# STM32F4_TFT-Proto_Adapter_FSMC.net
KiCad netlist of a schematic drawn in EAGLE
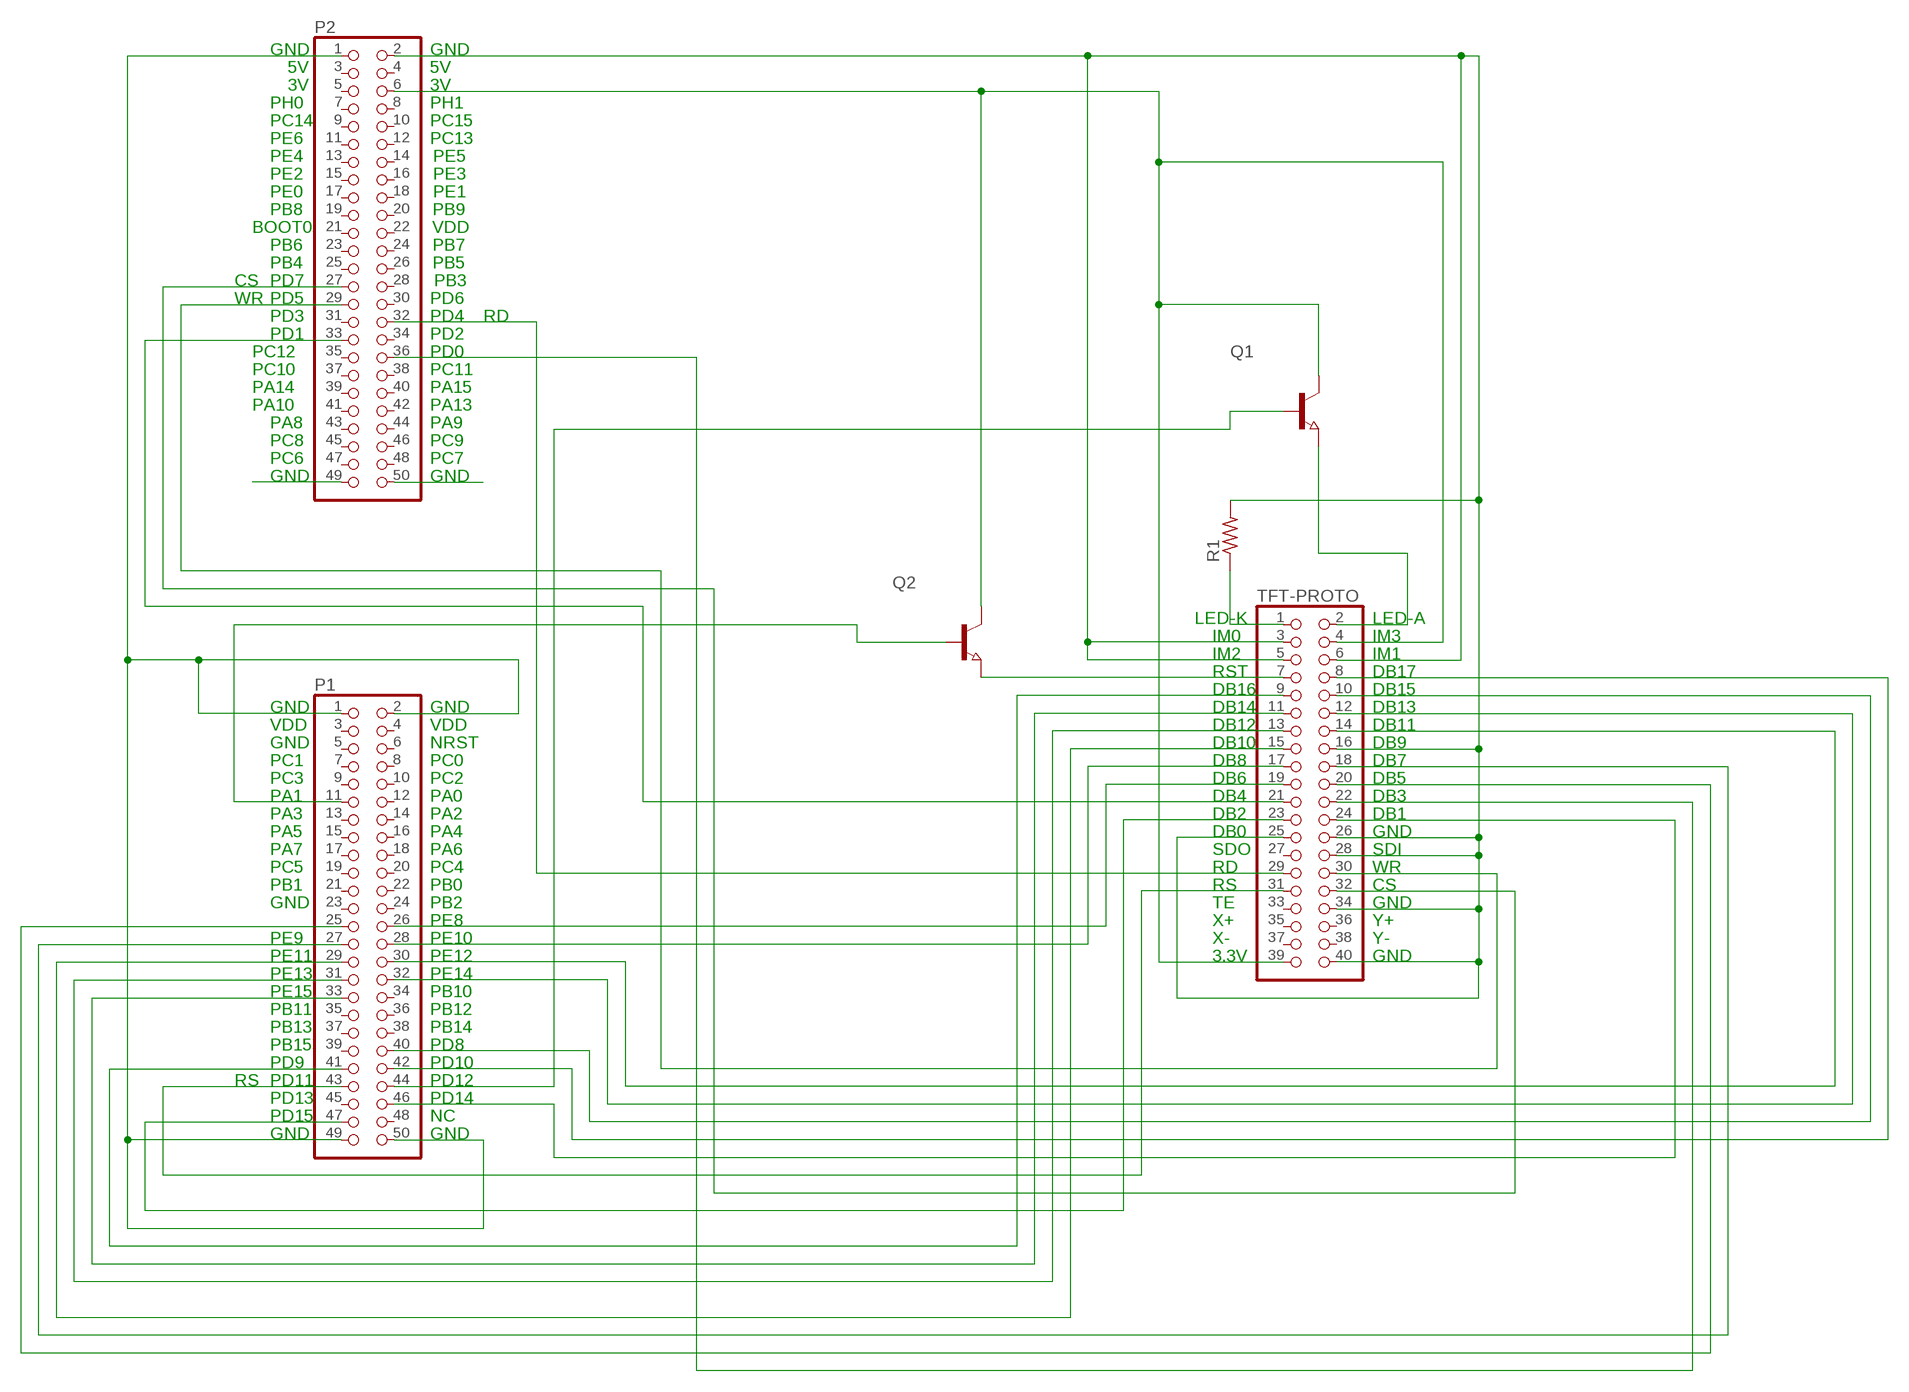
[diagram p0: schematic, sheet 1]

(export (version "E")
  (design (tool "Eeschema 10.0.6"))
  (components
    (comp (ref "P1")
      (value "PINHD-2X25")
      (footprint "eagle-import:2X25")
      (libsource (lib "eagle-import") (part "PINHD-2X25"))
    )
    (comp (ref "P2")
      (value "PINHD-2X25")
      (footprint "eagle-import:2X25")
      (libsource (lib "eagle-import") (part "PINHD-2X25"))
    )
    (comp (ref "Q1")
      (value "NPN-TRANSISTOR_SOT23")
      (footprint "eagle-import:SOT23")
      (libsource (lib "eagle-import") (part "NPN-TRANSISTOR_SOT23"))
    )
    (comp (ref "Q2")
      (value "NPN-TRANSISTOR_SOT23")
      (footprint "eagle-import:SOT23")
      (libsource (lib "eagle-import") (part "NPN-TRANSISTOR_SOT23"))
    )
    (comp (ref "R1")
      (value "R-US_R0805")
      (footprint "eagle-import:R0805")
      (libsource (lib "eagle-import") (part "R-US_R0805"))
    )
    (comp (ref "TFT-PROTO")
      (value "PINHD-2X20")
      (footprint "eagle-import:2X20")
      (libsource (lib "eagle-import") (part "PINHD-2X20"))
    )
  )
  (nets
    (net (code "1") (name "/GND") (class "Default")
      (node (ref "P1") (pin "1") (pinfunction "1_1") (pintype "passive"))
      (node (ref "P1") (pin "2") (pinfunction "2_2") (pintype "passive"))
      (node (ref "P1") (pin "49") (pinfunction "49_49") (pintype "passive"))
      (node (ref "P1") (pin "50") (pinfunction "50_50") (pintype "passive"))
      (node (ref "P2") (pin "1") (pinfunction "1_1") (pintype "passive"))
      (node (ref "P2") (pin "2") (pinfunction "2_2") (pintype "passive"))
      (node (ref "P2") (pin "49") (pinfunction "49_49") (pintype "passive"))
      (node (ref "P2") (pin "50") (pinfunction "50_50") (pintype "passive"))
      (node (ref "R1") (pin "2") (pinfunction "2_2") (pintype "passive"))
      (node (ref "TFT-PROTO") (pin "16") (pinfunction "16_16") (pintype "passive"))
      (node (ref "TFT-PROTO") (pin "25") (pinfunction "25_25") (pintype "passive"))
      (node (ref "TFT-PROTO") (pin "26") (pinfunction "26_26") (pintype "passive"))
      (node (ref "TFT-PROTO") (pin "28") (pinfunction "28_28") (pintype "passive"))
      (node (ref "TFT-PROTO") (pin "3") (pinfunction "3_3") (pintype "passive"))
      (node (ref "TFT-PROTO") (pin "34") (pinfunction "34_34") (pintype "passive"))
      (node (ref "TFT-PROTO") (pin "40") (pinfunction "40_40") (pintype "passive"))
      (node (ref "TFT-PROTO") (pin "5") (pinfunction "5_5") (pintype "passive"))
      (node (ref "TFT-PROTO") (pin "6") (pinfunction "6_6") (pintype "passive"))
    )
    (net (code "2") (name "Net-(P1-Pad25)") (class "Default")
      (node (ref "P1") (pin "25") (pinfunction "25_25") (pintype "passive"))
      (node (ref "TFT-PROTO") (pin "20") (pinfunction "20_20") (pintype "passive"))
    )
    (net (code "3") (name "Net-(P1-Pad26)") (class "Default")
      (node (ref "P1") (pin "26") (pinfunction "26_26") (pintype "passive"))
      (node (ref "TFT-PROTO") (pin "19") (pinfunction "19_19") (pintype "passive"))
    )
    (net (code "4") (name "Net-(P1-Pad27)") (class "Default")
      (node (ref "P1") (pin "27") (pinfunction "27_27") (pintype "passive"))
      (node (ref "TFT-PROTO") (pin "18") (pinfunction "18_18") (pintype "passive"))
    )
    (net (code "5") (name "Net-(P1-Pad28)") (class "Default")
      (node (ref "P1") (pin "28") (pinfunction "28_28") (pintype "passive"))
      (node (ref "TFT-PROTO") (pin "17") (pinfunction "17_17") (pintype "passive"))
    )
    (net (code "6") (name "Net-(P1-Pad29)") (class "Default")
      (node (ref "P1") (pin "29") (pinfunction "29_29") (pintype "passive"))
      (node (ref "TFT-PROTO") (pin "15") (pinfunction "15_15") (pintype "passive"))
    )
    (net (code "7") (name "Net-(P1-Pad30)") (class "Default")
      (node (ref "P1") (pin "30") (pinfunction "30_30") (pintype "passive"))
      (node (ref "TFT-PROTO") (pin "14") (pinfunction "14_14") (pintype "passive"))
    )
    (net (code "8") (name "Net-(P1-Pad31)") (class "Default")
      (node (ref "P1") (pin "31") (pinfunction "31_31") (pintype "passive"))
      (node (ref "TFT-PROTO") (pin "13") (pinfunction "13_13") (pintype "passive"))
    )
    (net (code "9") (name "Net-(P1-Pad32)") (class "Default")
      (node (ref "P1") (pin "32") (pinfunction "32_32") (pintype "passive"))
      (node (ref "TFT-PROTO") (pin "12") (pinfunction "12_12") (pintype "passive"))
    )
    (net (code "10") (name "Net-(P1-Pad33)") (class "Default")
      (node (ref "P1") (pin "33") (pinfunction "33_33") (pintype "passive"))
      (node (ref "TFT-PROTO") (pin "11") (pinfunction "11_11") (pintype "passive"))
    )
    (net (code "11") (name "Net-(P1-Pad40)") (class "Default")
      (node (ref "P1") (pin "40") (pinfunction "40_40") (pintype "passive"))
      (node (ref "TFT-PROTO") (pin "10") (pinfunction "10_10") (pintype "passive"))
    )
    (net (code "12") (name "Net-(P1-Pad41)") (class "Default")
      (node (ref "P1") (pin "41") (pinfunction "41_41") (pintype "passive"))
      (node (ref "TFT-PROTO") (pin "9") (pinfunction "9_9") (pintype "passive"))
    )
    (net (code "13") (name "Net-(P1-Pad42)") (class "Default")
      (node (ref "P1") (pin "42") (pinfunction "42_42") (pintype "passive"))
      (node (ref "TFT-PROTO") (pin "8") (pinfunction "8_8") (pintype "passive"))
    )
    (net (code "14") (name "Net-(P1-Pad43)") (class "Default")
      (node (ref "P1") (pin "43") (pinfunction "43_43") (pintype "passive"))
      (node (ref "TFT-PROTO") (pin "31") (pinfunction "31_31") (pintype "passive"))
    )
    (net (code "15") (name "Net-(P1-Pad46)") (class "Default")
      (node (ref "P1") (pin "46") (pinfunction "46_46") (pintype "passive"))
      (node (ref "TFT-PROTO") (pin "24") (pinfunction "24_24") (pintype "passive"))
    )
    (net (code "16") (name "Net-(P1-Pad47)") (class "Default")
      (node (ref "P1") (pin "47") (pinfunction "47_47") (pintype "passive"))
      (node (ref "TFT-PROTO") (pin "23") (pinfunction "23_23") (pintype "passive"))
    )
    (net (code "17") (name "Net-(P2-Pad27)") (class "Default")
      (node (ref "P2") (pin "27") (pinfunction "27_27") (pintype "passive"))
      (node (ref "TFT-PROTO") (pin "32") (pinfunction "32_32") (pintype "passive"))
    )
    (net (code "18") (name "Net-(P2-Pad29)") (class "Default")
      (node (ref "P2") (pin "29") (pinfunction "29_29") (pintype "passive"))
      (node (ref "TFT-PROTO") (pin "30") (pinfunction "30_30") (pintype "passive"))
    )
    (net (code "19") (name "Net-(P2-Pad32)") (class "Default")
      (node (ref "P2") (pin "32") (pinfunction "32_32") (pintype "passive"))
      (node (ref "TFT-PROTO") (pin "29") (pinfunction "29_29") (pintype "passive"))
    )
    (net (code "20") (name "Net-(P2-Pad33)") (class "Default")
      (node (ref "P2") (pin "33") (pinfunction "33_33") (pintype "passive"))
      (node (ref "TFT-PROTO") (pin "21") (pinfunction "21_21") (pintype "passive"))
    )
    (net (code "21") (name "Net-(P2-Pad36)") (class "Default")
      (node (ref "P2") (pin "36") (pinfunction "36_36") (pintype "passive"))
      (node (ref "TFT-PROTO") (pin "22") (pinfunction "22_22") (pintype "passive"))
    )
    (net (code "22") (name "Net-(Q1-B)") (class "Default")
      (node (ref "P1") (pin "44") (pinfunction "44_44") (pintype "passive"))
      (node (ref "Q1") (pin "1") (pinfunction "B_1") (pintype "passive"))
    )
    (net (code "23") (name "Net-(Q1-C)") (class "Default")
      (node (ref "P2") (pin "6") (pinfunction "6_6") (pintype "passive"))
      (node (ref "Q1") (pin "3") (pinfunction "C_3") (pintype "passive"))
      (node (ref "Q2") (pin "3") (pinfunction "C_3") (pintype "passive"))
      (node (ref "TFT-PROTO") (pin "39") (pinfunction "39_39") (pintype "passive"))
      (node (ref "TFT-PROTO") (pin "4") (pinfunction "4_4") (pintype "passive"))
    )
    (net (code "24") (name "Net-(Q1-E)") (class "Default")
      (node (ref "Q1") (pin "2") (pinfunction "E_2") (pintype "passive"))
      (node (ref "TFT-PROTO") (pin "2") (pinfunction "2_2") (pintype "passive"))
    )
    (net (code "25") (name "Net-(Q2-B)") (class "Default")
      (node (ref "P1") (pin "11") (pinfunction "11_11") (pintype "passive"))
      (node (ref "Q2") (pin "1") (pinfunction "B_1") (pintype "passive"))
    )
    (net (code "26") (name "Net-(Q2-E)") (class "Default")
      (node (ref "Q2") (pin "2") (pinfunction "E_2") (pintype "passive"))
      (node (ref "TFT-PROTO") (pin "7") (pinfunction "7_7") (pintype "passive"))
    )
    (net (code "27") (name "Net-(R1-Pad1)") (class "Default")
      (node (ref "R1") (pin "1") (pinfunction "1_1") (pintype "passive"))
      (node (ref "TFT-PROTO") (pin "1") (pinfunction "1_1") (pintype "passive"))
    )
    (net (code "28") (name "unconnected-(P1-Pad3)") (class "Default")
      (node (ref "P1") (pin "3") (pinfunction "3_3") (pintype "passive"))
    )
    (net (code "29") (name "unconnected-(P1-Pad4)") (class "Default")
      (node (ref "P1") (pin "4") (pinfunction "4_4") (pintype "passive"))
    )
    (net (code "30") (name "unconnected-(P1-Pad5)") (class "Default")
      (node (ref "P1") (pin "5") (pinfunction "5_5") (pintype "passive"))
    )
    (net (code "31") (name "unconnected-(P1-Pad6)") (class "Default")
      (node (ref "P1") (pin "6") (pinfunction "6_6") (pintype "passive"))
    )
    (net (code "32") (name "unconnected-(P1-Pad7)") (class "Default")
      (node (ref "P1") (pin "7") (pinfunction "7_7") (pintype "passive"))
    )
    (net (code "33") (name "unconnected-(P1-Pad8)") (class "Default")
      (node (ref "P1") (pin "8") (pinfunction "8_8") (pintype "passive"))
    )
    (net (code "34") (name "unconnected-(P1-Pad9)") (class "Default")
      (node (ref "P1") (pin "9") (pinfunction "9_9") (pintype "passive"))
    )
    (net (code "35") (name "unconnected-(P1-Pad10)") (class "Default")
      (node (ref "P1") (pin "10") (pinfunction "10_10") (pintype "passive"))
    )
    (net (code "36") (name "unconnected-(P1-Pad12)") (class "Default")
      (node (ref "P1") (pin "12") (pinfunction "12_12") (pintype "passive"))
    )
    (net (code "37") (name "unconnected-(P1-Pad13)") (class "Default")
      (node (ref "P1") (pin "13") (pinfunction "13_13") (pintype "passive"))
    )
    (net (code "38") (name "unconnected-(P1-Pad14)") (class "Default")
      (node (ref "P1") (pin "14") (pinfunction "14_14") (pintype "passive"))
    )
    (net (code "39") (name "unconnected-(P1-Pad15)") (class "Default")
      (node (ref "P1") (pin "15") (pinfunction "15_15") (pintype "passive"))
    )
    (net (code "40") (name "unconnected-(P1-Pad16)") (class "Default")
      (node (ref "P1") (pin "16") (pinfunction "16_16") (pintype "passive"))
    )
    (net (code "41") (name "unconnected-(P1-Pad17)") (class "Default")
      (node (ref "P1") (pin "17") (pinfunction "17_17") (pintype "passive"))
    )
    (net (code "42") (name "unconnected-(P1-Pad18)") (class "Default")
      (node (ref "P1") (pin "18") (pinfunction "18_18") (pintype "passive"))
    )
    (net (code "43") (name "unconnected-(P1-Pad19)") (class "Default")
      (node (ref "P1") (pin "19") (pinfunction "19_19") (pintype "passive"))
    )
    (net (code "44") (name "unconnected-(P1-Pad20)") (class "Default")
      (node (ref "P1") (pin "20") (pinfunction "20_20") (pintype "passive"))
    )
    (net (code "45") (name "unconnected-(P1-Pad21)") (class "Default")
      (node (ref "P1") (pin "21") (pinfunction "21_21") (pintype "passive"))
    )
    (net (code "46") (name "unconnected-(P1-Pad22)") (class "Default")
      (node (ref "P1") (pin "22") (pinfunction "22_22") (pintype "passive"))
    )
    (net (code "47") (name "unconnected-(P1-Pad23)") (class "Default")
      (node (ref "P1") (pin "23") (pinfunction "23_23") (pintype "passive"))
    )
    (net (code "48") (name "unconnected-(P1-Pad24)") (class "Default")
      (node (ref "P1") (pin "24") (pinfunction "24_24") (pintype "passive"))
    )
    (net (code "49") (name "unconnected-(P1-Pad34)") (class "Default")
      (node (ref "P1") (pin "34") (pinfunction "34_34") (pintype "passive"))
    )
    (net (code "50") (name "unconnected-(P1-Pad35)") (class "Default")
      (node (ref "P1") (pin "35") (pinfunction "35_35") (pintype "passive"))
    )
    (net (code "51") (name "unconnected-(P1-Pad36)") (class "Default")
      (node (ref "P1") (pin "36") (pinfunction "36_36") (pintype "passive"))
    )
    (net (code "52") (name "unconnected-(P1-Pad37)") (class "Default")
      (node (ref "P1") (pin "37") (pinfunction "37_37") (pintype "passive"))
    )
    (net (code "53") (name "unconnected-(P1-Pad38)") (class "Default")
      (node (ref "P1") (pin "38") (pinfunction "38_38") (pintype "passive"))
    )
    (net (code "54") (name "unconnected-(P1-Pad39)") (class "Default")
      (node (ref "P1") (pin "39") (pinfunction "39_39") (pintype "passive"))
    )
    (net (code "55") (name "unconnected-(P1-Pad45)") (class "Default")
      (node (ref "P1") (pin "45") (pinfunction "45_45") (pintype "passive"))
    )
    (net (code "56") (name "unconnected-(P1-Pad48)") (class "Default")
      (node (ref "P1") (pin "48") (pinfunction "48_48") (pintype "passive"))
    )
    (net (code "57") (name "unconnected-(P2-Pad3)") (class "Default")
      (node (ref "P2") (pin "3") (pinfunction "3_3") (pintype "passive"))
    )
    (net (code "58") (name "unconnected-(P2-Pad4)") (class "Default")
      (node (ref "P2") (pin "4") (pinfunction "4_4") (pintype "passive"))
    )
    (net (code "59") (name "unconnected-(P2-Pad5)") (class "Default")
      (node (ref "P2") (pin "5") (pinfunction "5_5") (pintype "passive"))
    )
    (net (code "60") (name "unconnected-(P2-Pad7)") (class "Default")
      (node (ref "P2") (pin "7") (pinfunction "7_7") (pintype "passive"))
    )
    (net (code "61") (name "unconnected-(P2-Pad8)") (class "Default")
      (node (ref "P2") (pin "8") (pinfunction "8_8") (pintype "passive"))
    )
    (net (code "62") (name "unconnected-(P2-Pad9)") (class "Default")
      (node (ref "P2") (pin "9") (pinfunction "9_9") (pintype "passive"))
    )
    (net (code "63") (name "unconnected-(P2-Pad10)") (class "Default")
      (node (ref "P2") (pin "10") (pinfunction "10_10") (pintype "passive"))
    )
    (net (code "64") (name "unconnected-(P2-Pad11)") (class "Default")
      (node (ref "P2") (pin "11") (pinfunction "11_11") (pintype "passive"))
    )
    (net (code "65") (name "unconnected-(P2-Pad12)") (class "Default")
      (node (ref "P2") (pin "12") (pinfunction "12_12") (pintype "passive"))
    )
    (net (code "66") (name "unconnected-(P2-Pad13)") (class "Default")
      (node (ref "P2") (pin "13") (pinfunction "13_13") (pintype "passive"))
    )
    (net (code "67") (name "unconnected-(P2-Pad14)") (class "Default")
      (node (ref "P2") (pin "14") (pinfunction "14_14") (pintype "passive"))
    )
    (net (code "68") (name "unconnected-(P2-Pad15)") (class "Default")
      (node (ref "P2") (pin "15") (pinfunction "15_15") (pintype "passive"))
    )
    (net (code "69") (name "unconnected-(P2-Pad16)") (class "Default")
      (node (ref "P2") (pin "16") (pinfunction "16_16") (pintype "passive"))
    )
    (net (code "70") (name "unconnected-(P2-Pad17)") (class "Default")
      (node (ref "P2") (pin "17") (pinfunction "17_17") (pintype "passive"))
    )
    (net (code "71") (name "unconnected-(P2-Pad18)") (class "Default")
      (node (ref "P2") (pin "18") (pinfunction "18_18") (pintype "passive"))
    )
    (net (code "72") (name "unconnected-(P2-Pad19)") (class "Default")
      (node (ref "P2") (pin "19") (pinfunction "19_19") (pintype "passive"))
    )
    (net (code "73") (name "unconnected-(P2-Pad20)") (class "Default")
      (node (ref "P2") (pin "20") (pinfunction "20_20") (pintype "passive"))
    )
    (net (code "74") (name "unconnected-(P2-Pad21)") (class "Default")
      (node (ref "P2") (pin "21") (pinfunction "21_21") (pintype "passive"))
    )
    (net (code "75") (name "unconnected-(P2-Pad22)") (class "Default")
      (node (ref "P2") (pin "22") (pinfunction "22_22") (pintype "passive"))
    )
    (net (code "76") (name "unconnected-(P2-Pad23)") (class "Default")
      (node (ref "P2") (pin "23") (pinfunction "23_23") (pintype "passive"))
    )
    (net (code "77") (name "unconnected-(P2-Pad24)") (class "Default")
      (node (ref "P2") (pin "24") (pinfunction "24_24") (pintype "passive"))
    )
    (net (code "78") (name "unconnected-(P2-Pad25)") (class "Default")
      (node (ref "P2") (pin "25") (pinfunction "25_25") (pintype "passive"))
    )
    (net (code "79") (name "unconnected-(P2-Pad26)") (class "Default")
      (node (ref "P2") (pin "26") (pinfunction "26_26") (pintype "passive"))
    )
    (net (code "80") (name "unconnected-(P2-Pad28)") (class "Default")
      (node (ref "P2") (pin "28") (pinfunction "28_28") (pintype "passive"))
    )
    (net (code "81") (name "unconnected-(P2-Pad30)") (class "Default")
      (node (ref "P2") (pin "30") (pinfunction "30_30") (pintype "passive"))
    )
    (net (code "82") (name "unconnected-(P2-Pad31)") (class "Default")
      (node (ref "P2") (pin "31") (pinfunction "31_31") (pintype "passive"))
    )
    (net (code "83") (name "unconnected-(P2-Pad34)") (class "Default")
      (node (ref "P2") (pin "34") (pinfunction "34_34") (pintype "passive"))
    )
    (net (code "84") (name "unconnected-(P2-Pad35)") (class "Default")
      (node (ref "P2") (pin "35") (pinfunction "35_35") (pintype "passive"))
    )
    (net (code "85") (name "unconnected-(P2-Pad37)") (class "Default")
      (node (ref "P2") (pin "37") (pinfunction "37_37") (pintype "passive"))
    )
    (net (code "86") (name "unconnected-(P2-Pad38)") (class "Default")
      (node (ref "P2") (pin "38") (pinfunction "38_38") (pintype "passive"))
    )
    (net (code "87") (name "unconnected-(P2-Pad39)") (class "Default")
      (node (ref "P2") (pin "39") (pinfunction "39_39") (pintype "passive"))
    )
    (net (code "88") (name "unconnected-(P2-Pad40)") (class "Default")
      (node (ref "P2") (pin "40") (pinfunction "40_40") (pintype "passive"))
    )
    (net (code "89") (name "unconnected-(P2-Pad41)") (class "Default")
      (node (ref "P2") (pin "41") (pinfunction "41_41") (pintype "passive"))
    )
    (net (code "90") (name "unconnected-(P2-Pad42)") (class "Default")
      (node (ref "P2") (pin "42") (pinfunction "42_42") (pintype "passive"))
    )
    (net (code "91") (name "unconnected-(P2-Pad43)") (class "Default")
      (node (ref "P2") (pin "43") (pinfunction "43_43") (pintype "passive"))
    )
    (net (code "92") (name "unconnected-(P2-Pad44)") (class "Default")
      (node (ref "P2") (pin "44") (pinfunction "44_44") (pintype "passive"))
    )
    (net (code "93") (name "unconnected-(P2-Pad45)") (class "Default")
      (node (ref "P2") (pin "45") (pinfunction "45_45") (pintype "passive"))
    )
    (net (code "94") (name "unconnected-(P2-Pad46)") (class "Default")
      (node (ref "P2") (pin "46") (pinfunction "46_46") (pintype "passive"))
    )
    (net (code "95") (name "unconnected-(P2-Pad47)") (class "Default")
      (node (ref "P2") (pin "47") (pinfunction "47_47") (pintype "passive"))
    )
    (net (code "96") (name "unconnected-(P2-Pad48)") (class "Default")
      (node (ref "P2") (pin "48") (pinfunction "48_48") (pintype "passive"))
    )
    (net (code "97") (name "unconnected-(TFT-PROTO-Pad27)") (class "Default")
      (node (ref "TFT-PROTO") (pin "27") (pinfunction "27_27") (pintype "passive"))
    )
    (net (code "98") (name "unconnected-(TFT-PROTO-Pad33)") (class "Default")
      (node (ref "TFT-PROTO") (pin "33") (pinfunction "33_33") (pintype "passive"))
    )
    (net (code "99") (name "unconnected-(TFT-PROTO-Pad35)") (class "Default")
      (node (ref "TFT-PROTO") (pin "35") (pinfunction "35_35") (pintype "passive"))
    )
    (net (code "100") (name "unconnected-(TFT-PROTO-Pad36)") (class "Default")
      (node (ref "TFT-PROTO") (pin "36") (pinfunction "36_36") (pintype "passive"))
    )
    (net (code "101") (name "unconnected-(TFT-PROTO-Pad37)") (class "Default")
      (node (ref "TFT-PROTO") (pin "37") (pinfunction "37_37") (pintype "passive"))
    )
    (net (code "102") (name "unconnected-(TFT-PROTO-Pad38)") (class "Default")
      (node (ref "TFT-PROTO") (pin "38") (pinfunction "38_38") (pintype "passive"))
    )
  )
)
